# connector_b.net
KiCad netlist of a schematic drawn in Altium Designer
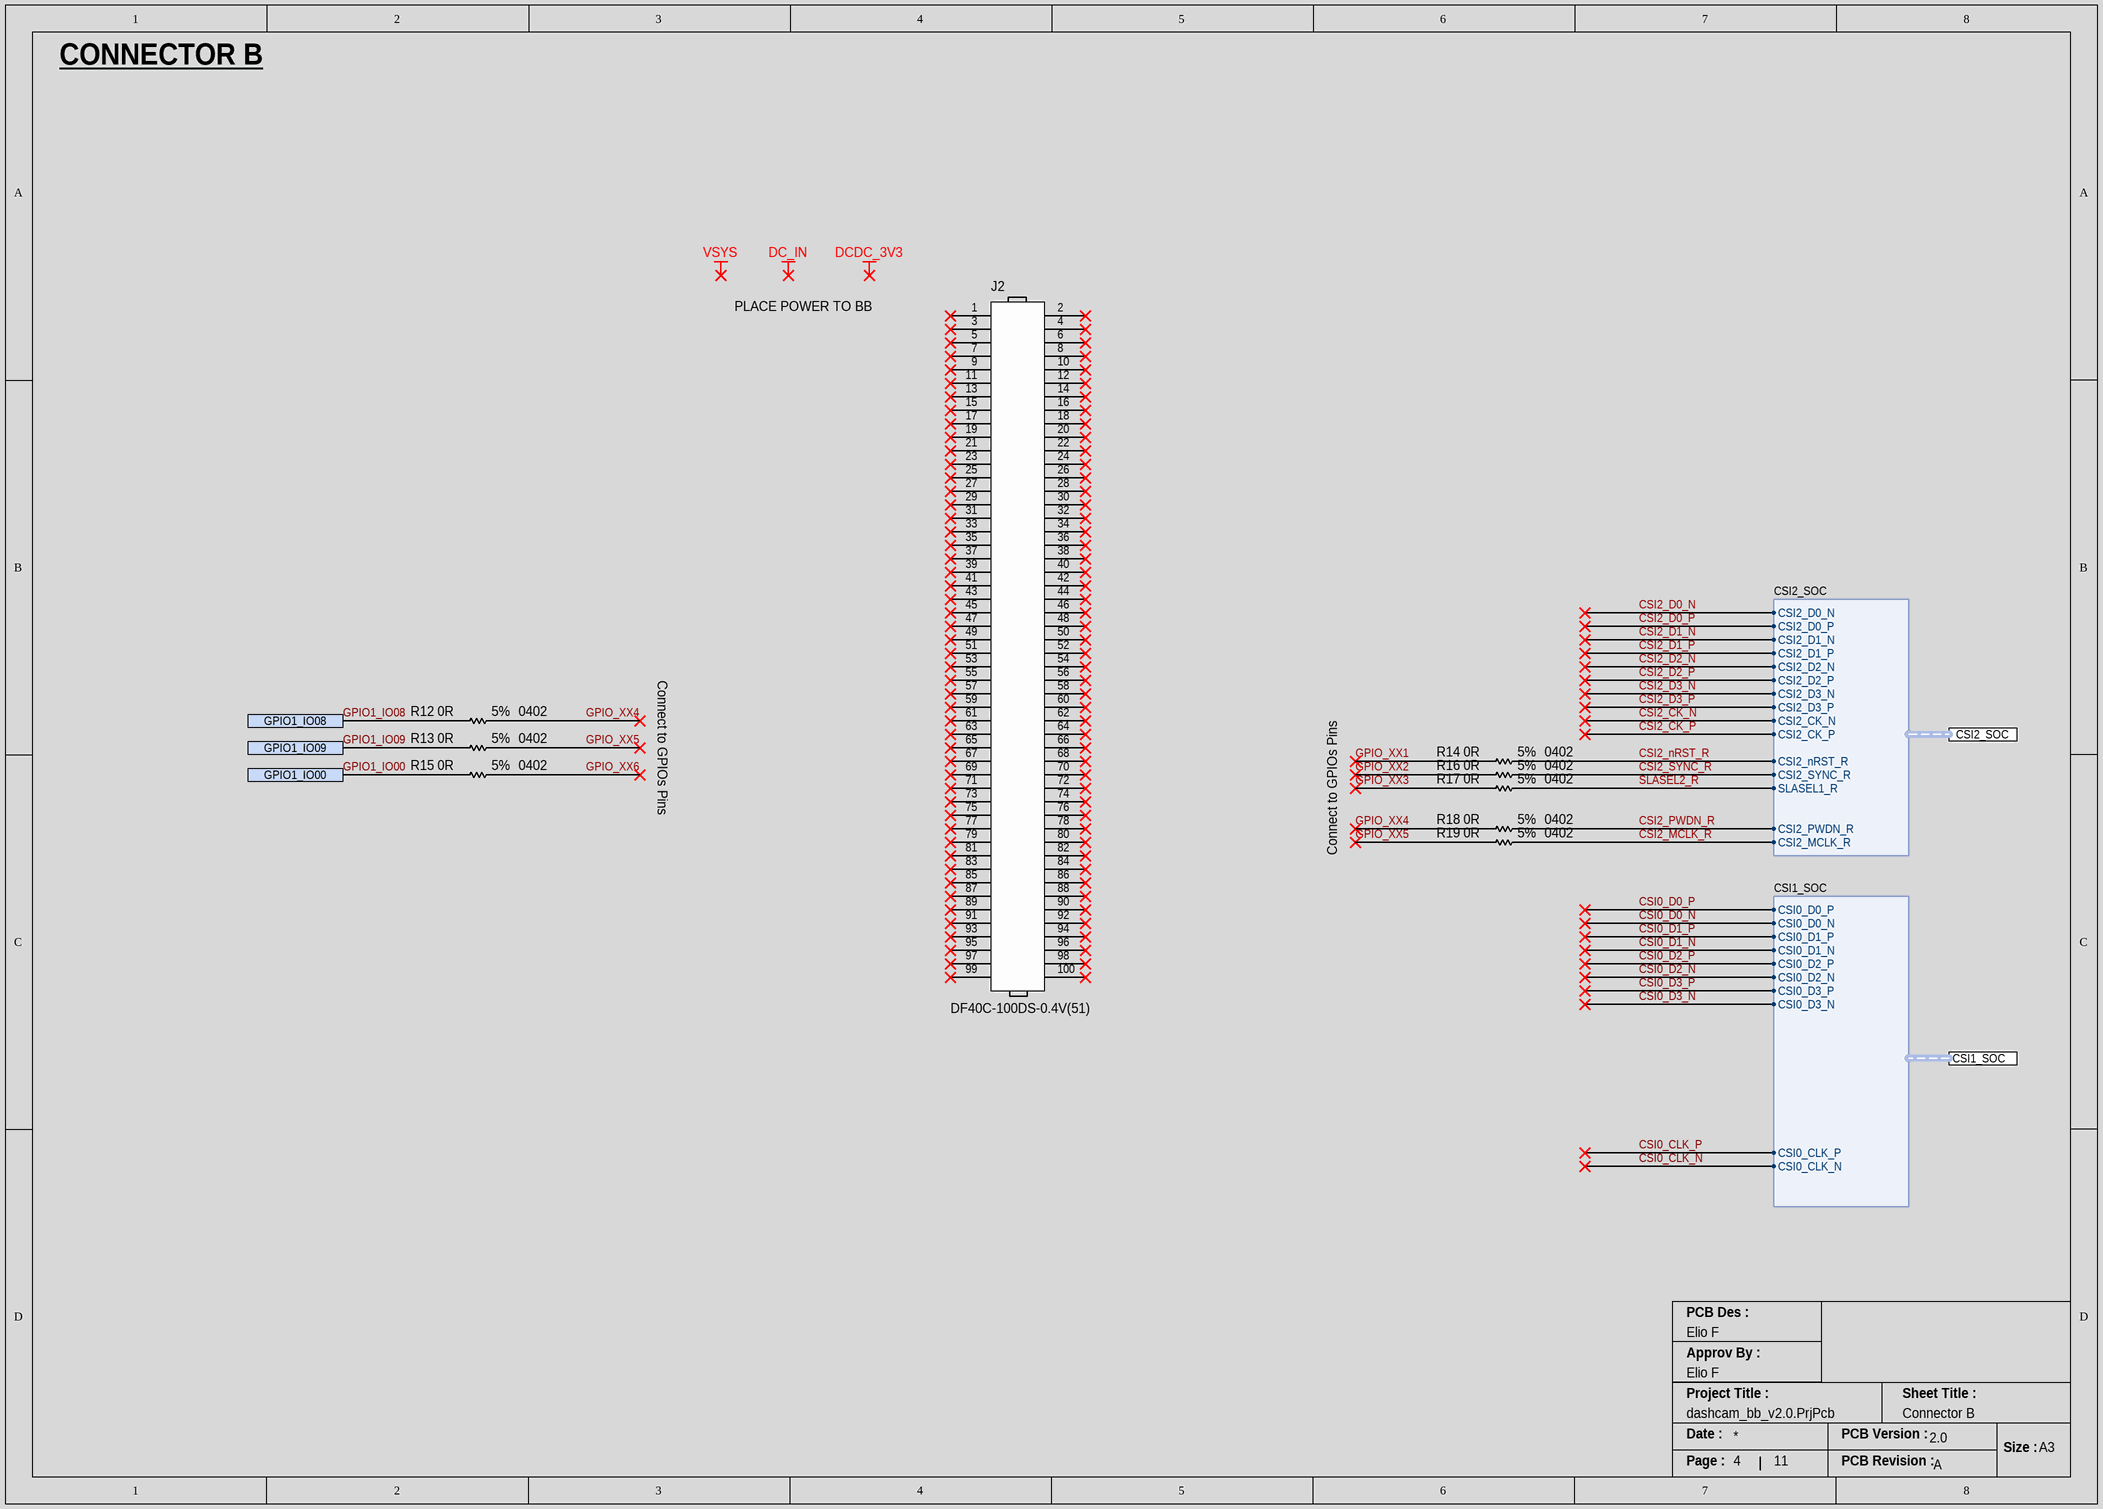
[diagram p0: connector_b.SchDoc]

(export (version "E")
  (design (tool "Eeschema 10.0.6"))
  (components
    (comp (ref "J2")
      (value "DF40C-100DS-0.4V(51)")
      (footprint "CONN_B2B_HIROSE_DF40C-100DS-0.4V(51)")
      (description "Board-to-Board Connector with 0.4-mm Pitch, 1.5 - 4.0-mm Height - DF40 Series (HIROSE ELECTRIC)")
      (fields (field (name "MANUFACTURER") "Hirose"))
      (libsource (lib "Electronic Devices_LIB") (part "CONN_B2B_100P_RE_DF40C-100DS-0.4V(51)"))
    )
    (comp (ref "R12")
      (value "ERJ-2GE0R00X")
      (footprint "RES_0402_RESC1005X04N")
      (description "SMD Chip Resistor, Jumper, 0 ohm, 100 mW, 0402 [1005 Metric], Thick Film, General Purpose")
      (fields
        (field (name "MANUFACTURER") "Panasonic")
        (field (name "CASE CODE (IMPERIAL)") "0402")
        (field (name "TOLERANCE") "5%")
        (field (name "RESISTANCE") "0R")
      )
      (libsource (lib "Electronic Devices_LIB") (part "RES_0R_5%_100mW_0402"))
    )
    (comp (ref "R13")
      (value "ERJ-2GE0R00X")
      (footprint "RES_0402_RESC1005X04N")
      (description "SMD Chip Resistor, Jumper, 0 ohm, 100 mW, 0402 [1005 Metric], Thick Film, General Purpose")
      (fields
        (field (name "MANUFACTURER") "Panasonic")
        (field (name "CASE CODE (IMPERIAL)") "0402")
        (field (name "TOLERANCE") "5%")
        (field (name "RESISTANCE") "0R")
      )
      (libsource (lib "Electronic Devices_LIB") (part "RES_0R_5%_100mW_0402"))
    )
    (comp (ref "R14")
      (value "ERJ-2GE0R00X")
      (footprint "RES_0402_RESC1005X04N")
      (description "SMD Chip Resistor, Jumper, 0 ohm, 100 mW, 0402 [1005 Metric], Thick Film, General Purpose")
      (fields
        (field (name "MANUFACTURER") "Panasonic")
        (field (name "CASE CODE (IMPERIAL)") "0402")
        (field (name "TOLERANCE") "5%")
        (field (name "RESISTANCE") "0R")
      )
      (libsource (lib "Electronic Devices_LIB") (part "RES_0R_5%_100mW_0402"))
    )
    (comp (ref "R15")
      (value "ERJ-2GE0R00X")
      (footprint "RES_0402_RESC1005X04N")
      (description "SMD Chip Resistor, Jumper, 0 ohm, 100 mW, 0402 [1005 Metric], Thick Film, General Purpose")
      (fields
        (field (name "MANUFACTURER") "Panasonic")
        (field (name "CASE CODE (IMPERIAL)") "0402")
        (field (name "TOLERANCE") "5%")
        (field (name "RESISTANCE") "0R")
      )
      (libsource (lib "Electronic Devices_LIB") (part "RES_0R_5%_100mW_0402"))
    )
    (comp (ref "R16")
      (value "ERJ-2GE0R00X")
      (footprint "RES_0402_RESC1005X04N")
      (description "SMD Chip Resistor, Jumper, 0 ohm, 100 mW, 0402 [1005 Metric], Thick Film, General Purpose")
      (fields
        (field (name "MANUFACTURER") "Panasonic")
        (field (name "CASE CODE (IMPERIAL)") "0402")
        (field (name "TOLERANCE") "5%")
        (field (name "RESISTANCE") "0R")
      )
      (libsource (lib "Electronic Devices_LIB") (part "RES_0R_5%_100mW_0402"))
    )
    (comp (ref "R17")
      (value "ERJ-2GE0R00X")
      (footprint "RES_0402_RESC1005X04N")
      (description "SMD Chip Resistor, Jumper, 0 ohm, 100 mW, 0402 [1005 Metric], Thick Film, General Purpose")
      (fields
        (field (name "MANUFACTURER") "Panasonic")
        (field (name "CASE CODE (IMPERIAL)") "0402")
        (field (name "TOLERANCE") "5%")
        (field (name "RESISTANCE") "0R")
      )
      (libsource (lib "Electronic Devices_LIB") (part "RES_0R_5%_100mW_0402"))
    )
    (comp (ref "R18")
      (value "ERJ-2GE0R00X")
      (footprint "RES_0402_RESC1005X04N")
      (description "SMD Chip Resistor, Jumper, 0 ohm, 100 mW, 0402 [1005 Metric], Thick Film, General Purpose")
      (fields
        (field (name "MANUFACTURER") "Panasonic")
        (field (name "CASE CODE (IMPERIAL)") "0402")
        (field (name "TOLERANCE") "5%")
        (field (name "RESISTANCE") "0R")
      )
      (libsource (lib "Electronic Devices_LIB") (part "RES_0R_5%_100mW_0402"))
    )
    (comp (ref "R19")
      (value "ERJ-2GE0R00X")
      (footprint "RES_0402_RESC1005X04N")
      (description "SMD Chip Resistor, Jumper, 0 ohm, 100 mW, 0402 [1005 Metric], Thick Film, General Purpose")
      (fields
        (field (name "MANUFACTURER") "Panasonic")
        (field (name "CASE CODE (IMPERIAL)") "0402")
        (field (name "TOLERANCE") "5%")
        (field (name "RESISTANCE") "0R")
      )
      (libsource (lib "Electronic Devices_LIB") (part "RES_0R_5%_100mW_0402"))
    )
  )
  (nets
    (net (code "23") (name "/CSI2_MCLK_R") (class "Default")
      (node (ref "R19") (pin "2") (pinfunction "2_2") (pintype "passive"))
    )
    (net (code "24") (name "/CSI2_PWDN_R") (class "Default")
      (node (ref "R18") (pin "2") (pinfunction "2_2") (pintype "passive"))
    )
    (net (code "25") (name "/CSI2_SYNC_R") (class "Default")
      (node (ref "R16") (pin "2") (pinfunction "2_2") (pintype "passive"))
    )
    (net (code "26") (name "/CSI2_nRST_R") (class "Default")
      (node (ref "R14") (pin "2") (pinfunction "2_2") (pintype "passive"))
    )
    (net (code "27") (name "/GPIO1_IO00") (class "Default")
      (node (ref "R15") (pin "1") (pinfunction "1_1") (pintype "passive"))
    )
    (net (code "28") (name "/GPIO1_IO08") (class "Default")
      (node (ref "R12") (pin "1") (pinfunction "1_1") (pintype "passive"))
    )
    (net (code "29") (name "/GPIO1_IO09") (class "Default")
      (node (ref "R13") (pin "1") (pinfunction "1_1") (pintype "passive"))
    )
    (net (code "30") (name "/GPIO_XX1") (class "Default")
      (node (ref "R14") (pin "1") (pinfunction "1_1") (pintype "passive+no_connect"))
    )
    (net (code "31") (name "/GPIO_XX2") (class "Default")
      (node (ref "R16") (pin "1") (pinfunction "1_1") (pintype "passive+no_connect"))
    )
    (net (code "32") (name "/GPIO_XX3") (class "Default")
      (node (ref "R17") (pin "1") (pinfunction "1_1") (pintype "passive+no_connect"))
    )
    (net (code "33") (name "/GPIO_XX4") (class "Default")
      (node (ref "R12") (pin "2") (pinfunction "2_2") (pintype "passive"))
      (node (ref "R18") (pin "1") (pinfunction "1_1") (pintype "passive"))
    )
    (net (code "34") (name "/GPIO_XX5") (class "Default")
      (node (ref "R13") (pin "2") (pinfunction "2_2") (pintype "passive"))
      (node (ref "R19") (pin "1") (pinfunction "1_1") (pintype "passive"))
    )
    (net (code "35") (name "/GPIO_XX6") (class "Default")
      (node (ref "R15") (pin "2") (pinfunction "2_2") (pintype "passive+no_connect"))
    )
    (net (code "36") (name "/SLASEL2_R") (class "Default")
      (node (ref "R17") (pin "2") (pinfunction "2_2") (pintype "passive"))
    )
    (net (code "42") (name "unconnected-(J2-Pad1)") (class "Default")
      (node (ref "J2") (pin "1") (pinfunction "1_1") (pintype "passive+no_connect"))
    )
    (net (code "43") (name "unconnected-(J2-Pad2)") (class "Default")
      (node (ref "J2") (pin "2") (pinfunction "2_2") (pintype "passive+no_connect"))
    )
    (net (code "44") (name "unconnected-(J2-Pad3)") (class "Default")
      (node (ref "J2") (pin "3") (pinfunction "3_3") (pintype "passive+no_connect"))
    )
    (net (code "45") (name "unconnected-(J2-Pad4)") (class "Default")
      (node (ref "J2") (pin "4") (pinfunction "4_4") (pintype "passive+no_connect"))
    )
    (net (code "46") (name "unconnected-(J2-Pad5)") (class "Default")
      (node (ref "J2") (pin "5") (pinfunction "5_5") (pintype "passive+no_connect"))
    )
    (net (code "47") (name "unconnected-(J2-Pad6)") (class "Default")
      (node (ref "J2") (pin "6") (pinfunction "6_6") (pintype "passive+no_connect"))
    )
    (net (code "48") (name "unconnected-(J2-Pad7)") (class "Default")
      (node (ref "J2") (pin "7") (pinfunction "7_7") (pintype "passive+no_connect"))
    )
    (net (code "49") (name "unconnected-(J2-Pad8)") (class "Default")
      (node (ref "J2") (pin "8") (pinfunction "8_8") (pintype "passive+no_connect"))
    )
    (net (code "50") (name "unconnected-(J2-Pad9)") (class "Default")
      (node (ref "J2") (pin "9") (pinfunction "9_9") (pintype "passive+no_connect"))
    )
    (net (code "51") (name "unconnected-(J2-Pad10)") (class "Default")
      (node (ref "J2") (pin "10") (pinfunction "10_10") (pintype "passive+no_connect"))
    )
    (net (code "52") (name "unconnected-(J2-Pad11)") (class "Default")
      (node (ref "J2") (pin "11") (pinfunction "11_11") (pintype "passive+no_connect"))
    )
    (net (code "53") (name "unconnected-(J2-Pad12)") (class "Default")
      (node (ref "J2") (pin "12") (pinfunction "12_12") (pintype "passive+no_connect"))
    )
    (net (code "54") (name "unconnected-(J2-Pad13)") (class "Default")
      (node (ref "J2") (pin "13") (pinfunction "13_13") (pintype "passive+no_connect"))
    )
    (net (code "55") (name "unconnected-(J2-Pad14)") (class "Default")
      (node (ref "J2") (pin "14") (pinfunction "14_14") (pintype "passive+no_connect"))
    )
    (net (code "56") (name "unconnected-(J2-Pad15)") (class "Default")
      (node (ref "J2") (pin "15") (pinfunction "15_15") (pintype "passive+no_connect"))
    )
    (net (code "57") (name "unconnected-(J2-Pad16)") (class "Default")
      (node (ref "J2") (pin "16") (pinfunction "16_16") (pintype "passive+no_connect"))
    )
    (net (code "58") (name "unconnected-(J2-Pad17)") (class "Default")
      (node (ref "J2") (pin "17") (pinfunction "17_17") (pintype "passive+no_connect"))
    )
    (net (code "59") (name "unconnected-(J2-Pad18)") (class "Default")
      (node (ref "J2") (pin "18") (pinfunction "18_18") (pintype "passive+no_connect"))
    )
    (net (code "60") (name "unconnected-(J2-Pad19)") (class "Default")
      (node (ref "J2") (pin "19") (pinfunction "19_19") (pintype "passive+no_connect"))
    )
    (net (code "61") (name "unconnected-(J2-Pad20)") (class "Default")
      (node (ref "J2") (pin "20") (pinfunction "20_20") (pintype "passive+no_connect"))
    )
    (net (code "62") (name "unconnected-(J2-Pad21)") (class "Default")
      (node (ref "J2") (pin "21") (pinfunction "21_21") (pintype "passive+no_connect"))
    )
    (net (code "63") (name "unconnected-(J2-Pad22)") (class "Default")
      (node (ref "J2") (pin "22") (pinfunction "22_22") (pintype "passive+no_connect"))
    )
    (net (code "64") (name "unconnected-(J2-Pad23)") (class "Default")
      (node (ref "J2") (pin "23") (pinfunction "23_23") (pintype "passive+no_connect"))
    )
    (net (code "65") (name "unconnected-(J2-Pad24)") (class "Default")
      (node (ref "J2") (pin "24") (pinfunction "24_24") (pintype "passive+no_connect"))
    )
    (net (code "66") (name "unconnected-(J2-Pad25)") (class "Default")
      (node (ref "J2") (pin "25") (pinfunction "25_25") (pintype "passive+no_connect"))
    )
    (net (code "67") (name "unconnected-(J2-Pad26)") (class "Default")
      (node (ref "J2") (pin "26") (pinfunction "26_26") (pintype "passive+no_connect"))
    )
    (net (code "68") (name "unconnected-(J2-Pad27)") (class "Default")
      (node (ref "J2") (pin "27") (pinfunction "27_27") (pintype "passive+no_connect"))
    )
    (net (code "69") (name "unconnected-(J2-Pad28)") (class "Default")
      (node (ref "J2") (pin "28") (pinfunction "28_28") (pintype "passive+no_connect"))
    )
    (net (code "70") (name "unconnected-(J2-Pad29)") (class "Default")
      (node (ref "J2") (pin "29") (pinfunction "29_29") (pintype "passive+no_connect"))
    )
    (net (code "71") (name "unconnected-(J2-Pad30)") (class "Default")
      (node (ref "J2") (pin "30") (pinfunction "30_30") (pintype "passive+no_connect"))
    )
    (net (code "72") (name "unconnected-(J2-Pad31)") (class "Default")
      (node (ref "J2") (pin "31") (pinfunction "31_31") (pintype "passive+no_connect"))
    )
    (net (code "73") (name "unconnected-(J2-Pad32)") (class "Default")
      (node (ref "J2") (pin "32") (pinfunction "32_32") (pintype "passive+no_connect"))
    )
    (net (code "74") (name "unconnected-(J2-Pad33)") (class "Default")
      (node (ref "J2") (pin "33") (pinfunction "33_33") (pintype "passive+no_connect"))
    )
    (net (code "75") (name "unconnected-(J2-Pad34)") (class "Default")
      (node (ref "J2") (pin "34") (pinfunction "34_34") (pintype "passive+no_connect"))
    )
    (net (code "76") (name "unconnected-(J2-Pad35)") (class "Default")
      (node (ref "J2") (pin "35") (pinfunction "35_35") (pintype "passive+no_connect"))
    )
    (net (code "77") (name "unconnected-(J2-Pad36)") (class "Default")
      (node (ref "J2") (pin "36") (pinfunction "36_36") (pintype "passive+no_connect"))
    )
    (net (code "78") (name "unconnected-(J2-Pad37)") (class "Default")
      (node (ref "J2") (pin "37") (pinfunction "37_37") (pintype "passive+no_connect"))
    )
    (net (code "79") (name "unconnected-(J2-Pad38)") (class "Default")
      (node (ref "J2") (pin "38") (pinfunction "38_38") (pintype "passive+no_connect"))
    )
    (net (code "80") (name "unconnected-(J2-Pad39)") (class "Default")
      (node (ref "J2") (pin "39") (pinfunction "39_39") (pintype "passive+no_connect"))
    )
    (net (code "81") (name "unconnected-(J2-Pad40)") (class "Default")
      (node (ref "J2") (pin "40") (pinfunction "40_40") (pintype "passive+no_connect"))
    )
    (net (code "82") (name "unconnected-(J2-Pad41)") (class "Default")
      (node (ref "J2") (pin "41") (pinfunction "41_41") (pintype "passive+no_connect"))
    )
    (net (code "83") (name "unconnected-(J2-Pad42)") (class "Default")
      (node (ref "J2") (pin "42") (pinfunction "42_42") (pintype "passive+no_connect"))
    )
    (net (code "84") (name "unconnected-(J2-Pad43)") (class "Default")
      (node (ref "J2") (pin "43") (pinfunction "43_43") (pintype "passive+no_connect"))
    )
    (net (code "85") (name "unconnected-(J2-Pad44)") (class "Default")
      (node (ref "J2") (pin "44") (pinfunction "44_44") (pintype "passive+no_connect"))
    )
    (net (code "86") (name "unconnected-(J2-Pad45)") (class "Default")
      (node (ref "J2") (pin "45") (pinfunction "45_45") (pintype "passive+no_connect"))
    )
    (net (code "87") (name "unconnected-(J2-Pad46)") (class "Default")
      (node (ref "J2") (pin "46") (pinfunction "46_46") (pintype "passive+no_connect"))
    )
    (net (code "88") (name "unconnected-(J2-Pad47)") (class "Default")
      (node (ref "J2") (pin "47") (pinfunction "47_47") (pintype "passive+no_connect"))
    )
    (net (code "89") (name "unconnected-(J2-Pad48)") (class "Default")
      (node (ref "J2") (pin "48") (pinfunction "48_48") (pintype "passive+no_connect"))
    )
    (net (code "90") (name "unconnected-(J2-Pad49)") (class "Default")
      (node (ref "J2") (pin "49") (pinfunction "49_49") (pintype "passive+no_connect"))
    )
    (net (code "91") (name "unconnected-(J2-Pad50)") (class "Default")
      (node (ref "J2") (pin "50") (pinfunction "50_50") (pintype "passive+no_connect"))
    )
    (net (code "92") (name "unconnected-(J2-Pad51)") (class "Default")
      (node (ref "J2") (pin "51") (pinfunction "51_51") (pintype "passive+no_connect"))
    )
    (net (code "93") (name "unconnected-(J2-Pad52)") (class "Default")
      (node (ref "J2") (pin "52") (pinfunction "52_52") (pintype "passive+no_connect"))
    )
    (net (code "94") (name "unconnected-(J2-Pad53)") (class "Default")
      (node (ref "J2") (pin "53") (pinfunction "53_53") (pintype "passive+no_connect"))
    )
    (net (code "95") (name "unconnected-(J2-Pad54)") (class "Default")
      (node (ref "J2") (pin "54") (pinfunction "54_54") (pintype "passive+no_connect"))
    )
    (net (code "96") (name "unconnected-(J2-Pad55)") (class "Default")
      (node (ref "J2") (pin "55") (pinfunction "55_55") (pintype "passive+no_connect"))
    )
    (net (code "97") (name "unconnected-(J2-Pad56)") (class "Default")
      (node (ref "J2") (pin "56") (pinfunction "56_56") (pintype "passive+no_connect"))
    )
    (net (code "98") (name "unconnected-(J2-Pad57)") (class "Default")
      (node (ref "J2") (pin "57") (pinfunction "57_57") (pintype "passive+no_connect"))
    )
    (net (code "99") (name "unconnected-(J2-Pad58)") (class "Default")
      (node (ref "J2") (pin "58") (pinfunction "58_58") (pintype "passive+no_connect"))
    )
    (net (code "100") (name "unconnected-(J2-Pad59)") (class "Default")
      (node (ref "J2") (pin "59") (pinfunction "59_59") (pintype "passive+no_connect"))
    )
    (net (code "101") (name "unconnected-(J2-Pad60)") (class "Default")
      (node (ref "J2") (pin "60") (pinfunction "60_60") (pintype "passive+no_connect"))
    )
    (net (code "102") (name "unconnected-(J2-Pad61)") (class "Default")
      (node (ref "J2") (pin "61") (pinfunction "61_61") (pintype "passive+no_connect"))
    )
    (net (code "103") (name "unconnected-(J2-Pad62)") (class "Default")
      (node (ref "J2") (pin "62") (pinfunction "62_62") (pintype "passive+no_connect"))
    )
    (net (code "104") (name "unconnected-(J2-Pad63)") (class "Default")
      (node (ref "J2") (pin "63") (pinfunction "63_63") (pintype "passive+no_connect"))
    )
    (net (code "105") (name "unconnected-(J2-Pad64)") (class "Default")
      (node (ref "J2") (pin "64") (pinfunction "64_64") (pintype "passive+no_connect"))
    )
    (net (code "106") (name "unconnected-(J2-Pad65)") (class "Default")
      (node (ref "J2") (pin "65") (pinfunction "65_65") (pintype "passive+no_connect"))
    )
    (net (code "107") (name "unconnected-(J2-Pad66)") (class "Default")
      (node (ref "J2") (pin "66") (pinfunction "66_66") (pintype "passive+no_connect"))
    )
    (net (code "108") (name "unconnected-(J2-Pad67)") (class "Default")
      (node (ref "J2") (pin "67") (pinfunction "67_67") (pintype "passive+no_connect"))
    )
    (net (code "109") (name "unconnected-(J2-Pad68)") (class "Default")
      (node (ref "J2") (pin "68") (pinfunction "68_68") (pintype "passive+no_connect"))
    )
    (net (code "110") (name "unconnected-(J2-Pad69)") (class "Default")
      (node (ref "J2") (pin "69") (pinfunction "69_69") (pintype "passive+no_connect"))
    )
    (net (code "111") (name "unconnected-(J2-Pad70)") (class "Default")
      (node (ref "J2") (pin "70") (pinfunction "70_70") (pintype "passive+no_connect"))
    )
    (net (code "112") (name "unconnected-(J2-Pad71)") (class "Default")
      (node (ref "J2") (pin "71") (pinfunction "71_71") (pintype "passive+no_connect"))
    )
    (net (code "113") (name "unconnected-(J2-Pad72)") (class "Default")
      (node (ref "J2") (pin "72") (pinfunction "72_72") (pintype "passive+no_connect"))
    )
    (net (code "114") (name "unconnected-(J2-Pad73)") (class "Default")
      (node (ref "J2") (pin "73") (pinfunction "73_73") (pintype "passive+no_connect"))
    )
    (net (code "115") (name "unconnected-(J2-Pad74)") (class "Default")
      (node (ref "J2") (pin "74") (pinfunction "74_74") (pintype "passive+no_connect"))
    )
    (net (code "116") (name "unconnected-(J2-Pad75)") (class "Default")
      (node (ref "J2") (pin "75") (pinfunction "75_75") (pintype "passive+no_connect"))
    )
    (net (code "117") (name "unconnected-(J2-Pad76)") (class "Default")
      (node (ref "J2") (pin "76") (pinfunction "76_76") (pintype "passive+no_connect"))
    )
    (net (code "118") (name "unconnected-(J2-Pad77)") (class "Default")
      (node (ref "J2") (pin "77") (pinfunction "77_77") (pintype "passive+no_connect"))
    )
    (net (code "119") (name "unconnected-(J2-Pad78)") (class "Default")
      (node (ref "J2") (pin "78") (pinfunction "78_78") (pintype "passive+no_connect"))
    )
    (net (code "120") (name "unconnected-(J2-Pad79)") (class "Default")
      (node (ref "J2") (pin "79") (pinfunction "79_79") (pintype "passive+no_connect"))
    )
    (net (code "121") (name "unconnected-(J2-Pad80)") (class "Default")
      (node (ref "J2") (pin "80") (pinfunction "80_80") (pintype "passive+no_connect"))
    )
    (net (code "122") (name "unconnected-(J2-Pad81)") (class "Default")
      (node (ref "J2") (pin "81") (pinfunction "81_81") (pintype "passive+no_connect"))
    )
    (net (code "123") (name "unconnected-(J2-Pad82)") (class "Default")
      (node (ref "J2") (pin "82") (pinfunction "82_82") (pintype "passive+no_connect"))
    )
    (net (code "124") (name "unconnected-(J2-Pad83)") (class "Default")
      (node (ref "J2") (pin "83") (pinfunction "83_83") (pintype "passive+no_connect"))
    )
    (net (code "125") (name "unconnected-(J2-Pad84)") (class "Default")
      (node (ref "J2") (pin "84") (pinfunction "84_84") (pintype "passive+no_connect"))
    )
    (net (code "126") (name "unconnected-(J2-Pad85)") (class "Default")
      (node (ref "J2") (pin "85") (pinfunction "85_85") (pintype "passive+no_connect"))
    )
    (net (code "127") (name "unconnected-(J2-Pad86)") (class "Default")
      (node (ref "J2") (pin "86") (pinfunction "86_86") (pintype "passive+no_connect"))
    )
    (net (code "128") (name "unconnected-(J2-Pad87)") (class "Default")
      (node (ref "J2") (pin "87") (pinfunction "87_87") (pintype "passive+no_connect"))
    )
    (net (code "129") (name "unconnected-(J2-Pad88)") (class "Default")
      (node (ref "J2") (pin "88") (pinfunction "88_88") (pintype "passive+no_connect"))
    )
    (net (code "130") (name "unconnected-(J2-Pad89)") (class "Default")
      (node (ref "J2") (pin "89") (pinfunction "89_89") (pintype "passive+no_connect"))
    )
    (net (code "131") (name "unconnected-(J2-Pad90)") (class "Default")
      (node (ref "J2") (pin "90") (pinfunction "90_90") (pintype "passive+no_connect"))
    )
    (net (code "132") (name "unconnected-(J2-Pad91)") (class "Default")
      (node (ref "J2") (pin "91") (pinfunction "91_91") (pintype "passive+no_connect"))
    )
    (net (code "133") (name "unconnected-(J2-Pad92)") (class "Default")
      (node (ref "J2") (pin "92") (pinfunction "92_92") (pintype "passive+no_connect"))
    )
    (net (code "134") (name "unconnected-(J2-Pad93)") (class "Default")
      (node (ref "J2") (pin "93") (pinfunction "93_93") (pintype "passive+no_connect"))
    )
    (net (code "135") (name "unconnected-(J2-Pad94)") (class "Default")
      (node (ref "J2") (pin "94") (pinfunction "94_94") (pintype "passive+no_connect"))
    )
    (net (code "136") (name "unconnected-(J2-Pad95)") (class "Default")
      (node (ref "J2") (pin "95") (pinfunction "95_95") (pintype "passive+no_connect"))
    )
    (net (code "137") (name "unconnected-(J2-Pad96)") (class "Default")
      (node (ref "J2") (pin "96") (pinfunction "96_96") (pintype "passive+no_connect"))
    )
    (net (code "138") (name "unconnected-(J2-Pad97)") (class "Default")
      (node (ref "J2") (pin "97") (pinfunction "97_97") (pintype "passive+no_connect"))
    )
    (net (code "139") (name "unconnected-(J2-Pad98)") (class "Default")
      (node (ref "J2") (pin "98") (pinfunction "98_98") (pintype "passive+no_connect"))
    )
    (net (code "140") (name "unconnected-(J2-Pad99)") (class "Default")
      (node (ref "J2") (pin "99") (pinfunction "99_99") (pintype "passive+no_connect"))
    )
    (net (code "141") (name "unconnected-(J2-Pad100)") (class "Default")
      (node (ref "J2") (pin "100") (pinfunction "100_100") (pintype "passive+no_connect"))
    )
  )
)
